# Aquila-2018-Under2.net
KiCad netlist of a schematic drawn in EAGLE
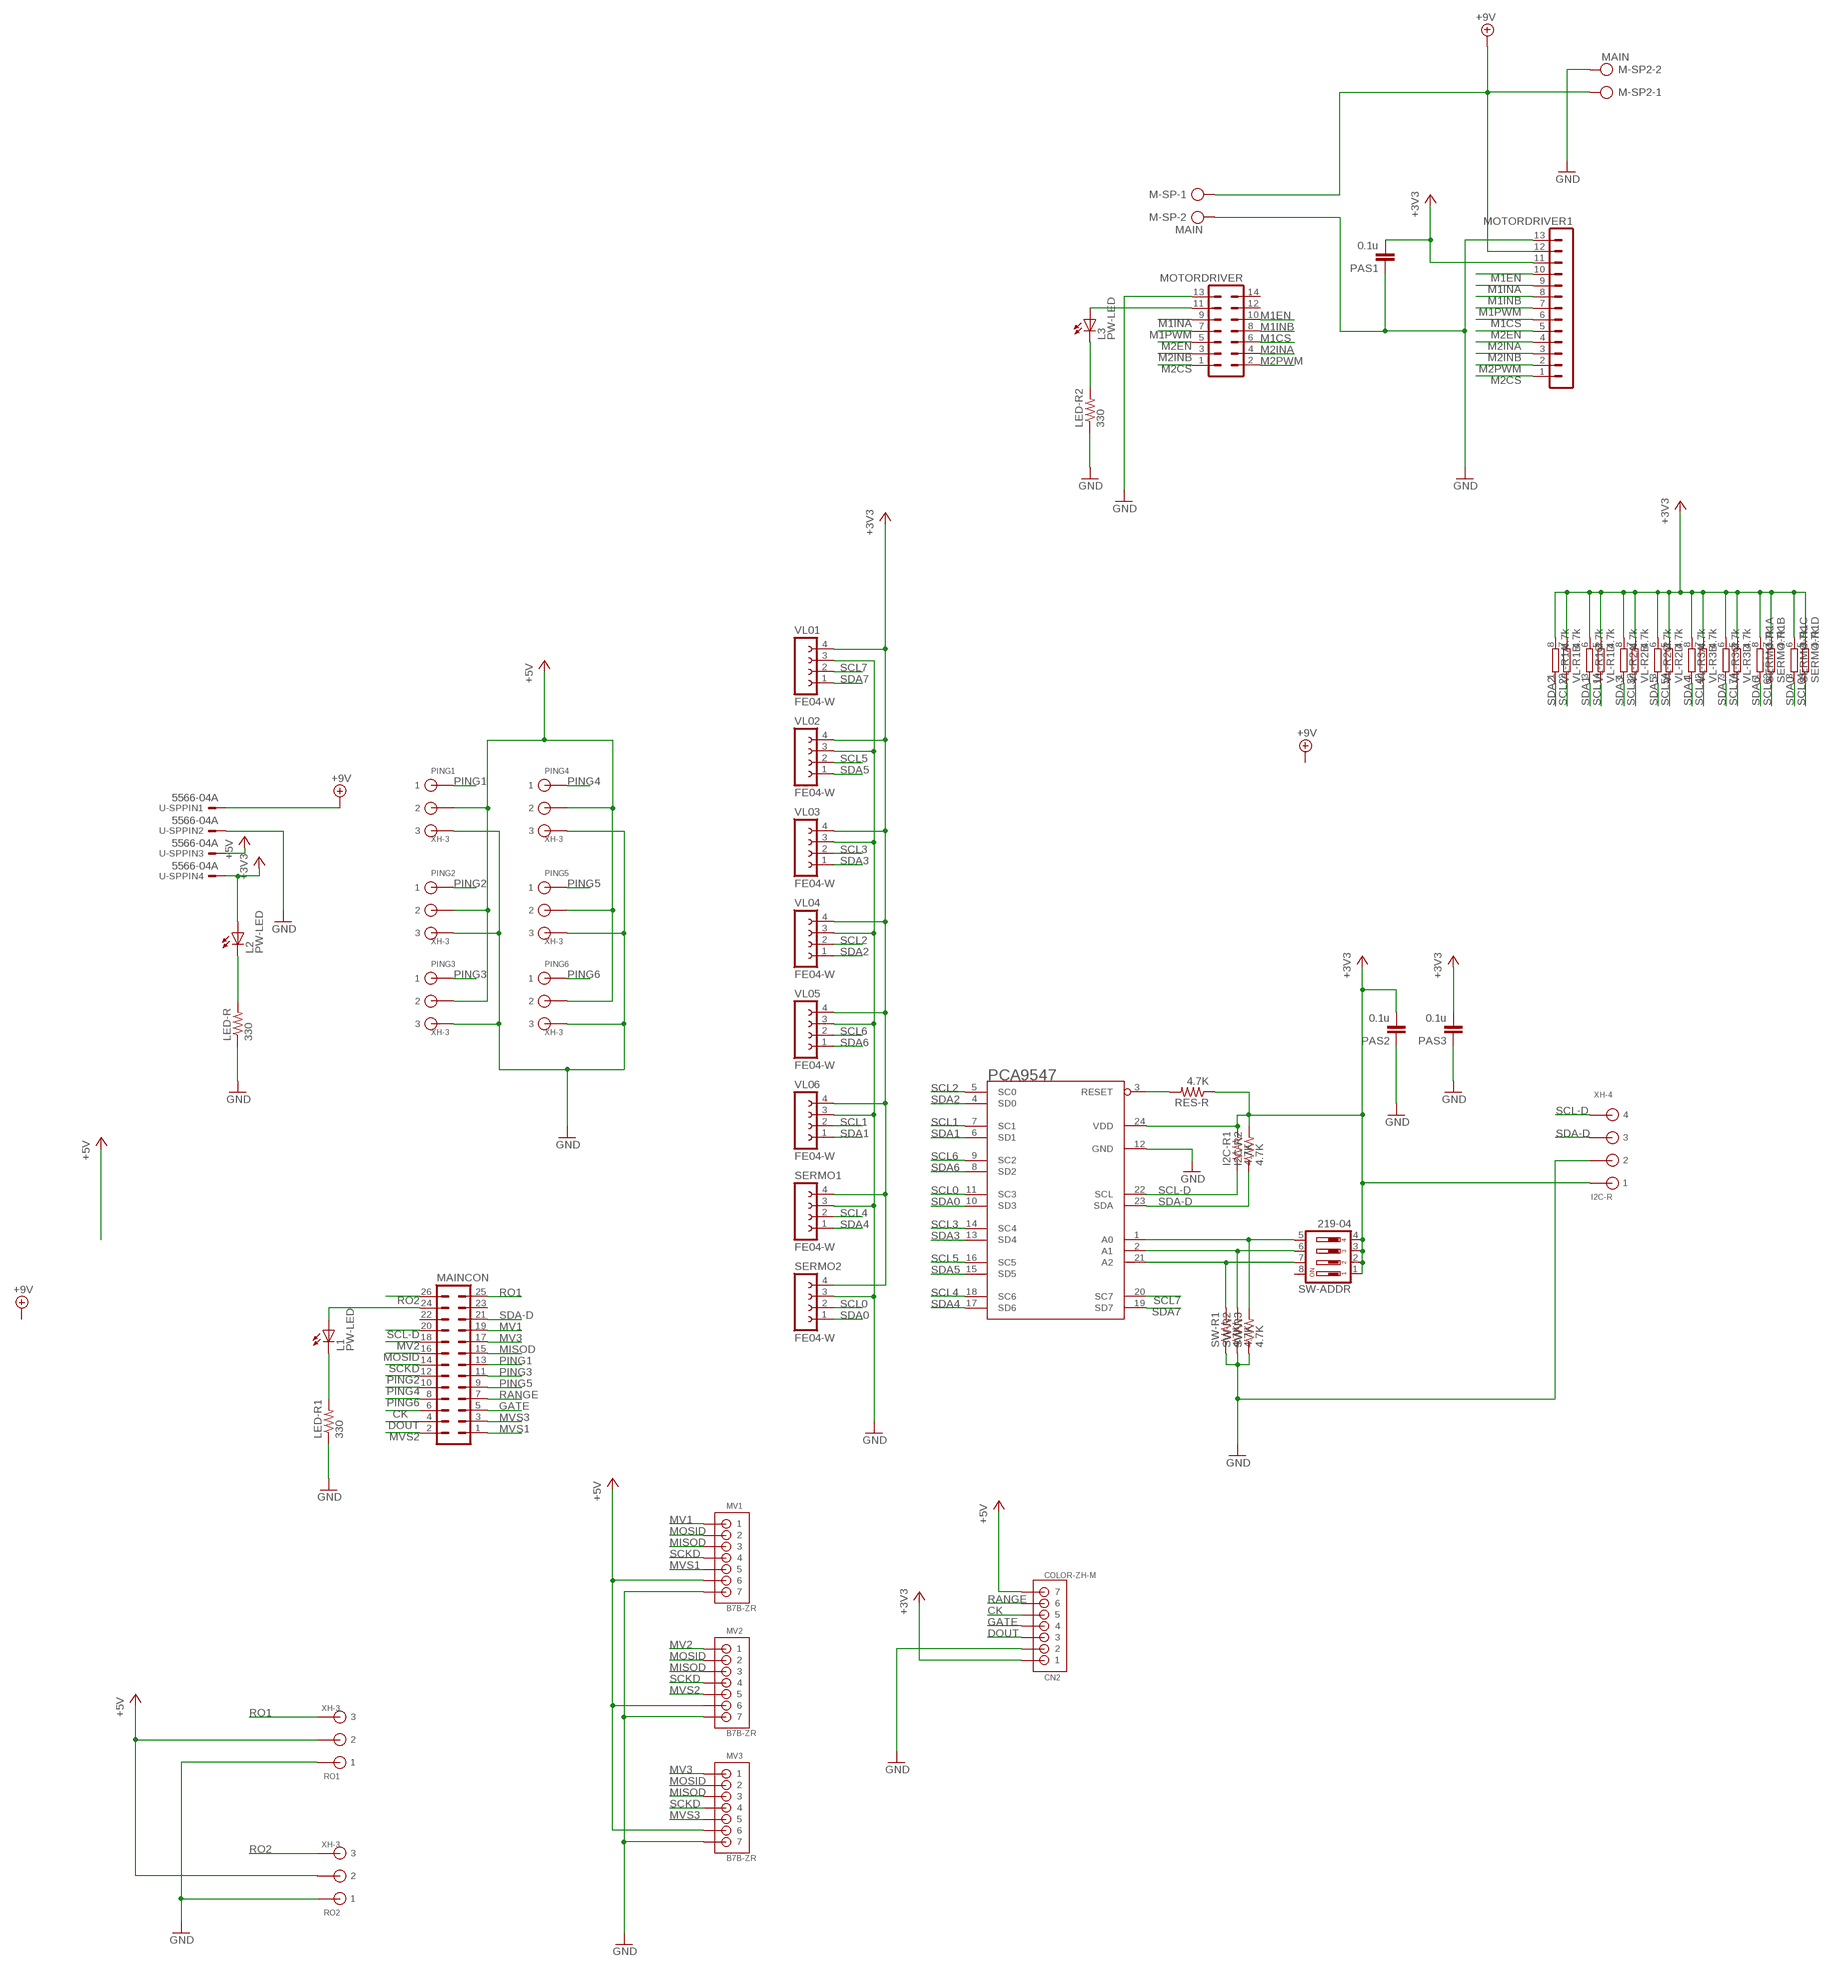
[diagram p0: schematic, sheet 1]

(export (version "E")
  (design (tool "Eeschema 10.0.6"))
  (components
    (comp (ref "CN2")
      (value "COLOR-ZH-M")
      (footprint "eagle-import:B7B-ZR")
      (libsource (lib "eagle-import") (part "B7B-ZR"))
    )
    (comp (ref "I2C-R")
      (value "XH-4")
      (footprint "eagle-import:CON4")
      (libsource (lib "eagle-import") (part "XH-4"))
    )
    (comp (ref "I2C-R1")
      (value "4.7K")
      (footprint "eagle-import:R0805")
      (libsource (lib "eagle-import") (part "R-US_R0805"))
    )
    (comp (ref "I2C-R2")
      (value "4.7K")
      (footprint "eagle-import:R0805")
      (libsource (lib "eagle-import") (part "R-US_R0805"))
    )
    (comp (ref "L1")
      (value "PW-LED")
      (footprint "eagle-import:CHIPLED_0805")
      (libsource (lib "eagle-import") (part "LEDCHIPLED_0805"))
    )
    (comp (ref "L2")
      (value "PW-LED")
      (footprint "eagle-import:CHIPLED_0805")
      (libsource (lib "eagle-import") (part "LEDCHIPLED_0805"))
    )
    (comp (ref "L3")
      (value "PW-LED")
      (footprint "eagle-import:CHIPLED_0805")
      (libsource (lib "eagle-import") (part "LEDCHIPLED_0805"))
    )
    (comp (ref "LED-R")
      (value "330")
      (footprint "eagle-import:R0805")
      (libsource (lib "eagle-import") (part "R-US_R0805"))
    )
    (comp (ref "LED-R1")
      (value "330")
      (footprint "eagle-import:R0805")
      (libsource (lib "eagle-import") (part "R-US_R0805"))
    )
    (comp (ref "LED-R2")
      (value "330")
      (footprint "eagle-import:R0805")
      (libsource (lib "eagle-import") (part "R-US_R0805"))
    )
    (comp (ref "M-SP")
      (value "MAIN")
      (footprint "eagle-import:AK500_2")
      (libsource (lib "eagle-import") (part "AK500/2"))
    )
    (comp (ref "M-SP2")
      (value "MAIN")
      (footprint "eagle-import:AK500_2")
      (libsource (lib "eagle-import") (part "AK500/2"))
    )
    (comp (ref "MAINCON")
      (value "ML26")
      (footprint "eagle-import:ML26")
      (libsource (lib "eagle-import") (part "ML26"))
    )
    (comp (ref "MOTORDRIVER")
      (value "ML14")
      (footprint "eagle-import:ML14")
      (libsource (lib "eagle-import") (part "ML14"))
    )
    (comp (ref "MOTORDRIVER1")
      (value "MA13-1")
      (footprint "eagle-import:MA13-1")
      (libsource (lib "eagle-import") (part "MA13-1"))
    )
    (comp (ref "MV1")
      (value "B7B-ZR")
      (footprint "eagle-import:B7B-ZR")
      (libsource (lib "eagle-import") (part "B7B-ZR"))
    )
    (comp (ref "MV2")
      (value "B7B-ZR")
      (footprint "eagle-import:B7B-ZR")
      (libsource (lib "eagle-import") (part "B7B-ZR"))
    )
    (comp (ref "MV3")
      (value "B7B-ZR")
      (footprint "eagle-import:B7B-ZR")
      (libsource (lib "eagle-import") (part "B7B-ZR"))
    )
    (comp (ref "PAS1")
      (value "0.1u")
      (footprint "eagle-import:C0805")
      (fields (field (name "SPICEPREFIX") "B"))
      (libsource (lib "eagle-import") (part "C-EUC0805"))
    )
    (comp (ref "PAS2")
      (value "0.1u")
      (footprint "eagle-import:C0805")
      (fields (field (name "SPICEPREFIX") "B"))
      (libsource (lib "eagle-import") (part "C-EUC0805"))
    )
    (comp (ref "PAS3")
      (value "0.1u")
      (footprint "eagle-import:C0805")
      (fields (field (name "SPICEPREFIX") "B"))
      (libsource (lib "eagle-import") (part "C-EUC0805"))
    )
    (comp (ref "PCA9547")
      (value "PCA9547")
      (footprint "eagle-import:SO24L")
      (libsource (lib "eagle-import") (part "PCA9547"))
    )
    (comp (ref "PING1")
      (value "XH-3")
      (footprint "eagle-import:CON3")
      (libsource (lib "eagle-import") (part "XH-3"))
    )
    (comp (ref "PING2")
      (value "XH-3")
      (footprint "eagle-import:CON3")
      (libsource (lib "eagle-import") (part "XH-3"))
    )
    (comp (ref "PING3")
      (value "XH-3")
      (footprint "eagle-import:CON3")
      (libsource (lib "eagle-import") (part "XH-3"))
    )
    (comp (ref "PING4")
      (value "XH-3")
      (footprint "eagle-import:CON3")
      (libsource (lib "eagle-import") (part "XH-3"))
    )
    (comp (ref "PING5")
      (value "XH-3")
      (footprint "eagle-import:CON3")
      (libsource (lib "eagle-import") (part "XH-3"))
    )
    (comp (ref "PING6")
      (value "XH-3")
      (footprint "eagle-import:CON3")
      (libsource (lib "eagle-import") (part "XH-3"))
    )
    (comp (ref "RES-R")
      (value "4.7K")
      (footprint "eagle-import:R0805")
      (libsource (lib "eagle-import") (part "R-US_R0805"))
    )
    (comp (ref "RO1")
      (value "XH-3")
      (footprint "eagle-import:CON3")
      (libsource (lib "eagle-import") (part "forprint_XH-3"))
    )
    (comp (ref "RO2")
      (value "XH-3")
      (footprint "eagle-import:CON3")
      (libsource (lib "eagle-import") (part "forprint_XH-3"))
    )
    (comp (ref "SERMO-R1")
      (value "4.7k")
      (footprint "eagle-import:EXB28V")
      (libsource (lib "eagle-import") (part "4R-NEXB28V"))
    )
    (comp (ref "SERMO1")
      (value "FE04-W")
      (footprint "eagle-import:FE04-W")
      (libsource (lib "eagle-import") (part "FE04-W"))
    )
    (comp (ref "SERMO2")
      (value "FE04-W")
      (footprint "eagle-import:FE04-W")
      (libsource (lib "eagle-import") (part "FE04-W"))
    )
    (comp (ref "SW-ADDR")
      (value "219-04")
      (footprint "eagle-import:CTS-219-04")
      (libsource (lib "eagle-import") (part "219-04"))
    )
    (comp (ref "SW-R1")
      (value "4.7K")
      (footprint "eagle-import:R0805")
      (libsource (lib "eagle-import") (part "R-US_R0805"))
    )
    (comp (ref "SW-R2")
      (value "4.7K")
      (footprint "eagle-import:R0805")
      (libsource (lib "eagle-import") (part "R-US_R0805"))
    )
    (comp (ref "SW-R3")
      (value "4.7K")
      (footprint "eagle-import:R0805")
      (libsource (lib "eagle-import") (part "R-US_R0805"))
    )
    (comp (ref "U-SP")
      (value "5566-04A")
      (footprint "eagle-import:5566-04A")
      (libsource (lib "eagle-import") (part "5566-04A"))
    )
    (comp (ref "VL-R1")
      (value "4.7k")
      (footprint "eagle-import:EXB28V")
      (libsource (lib "eagle-import") (part "4R-NEXB28V"))
    )
    (comp (ref "VL-R2")
      (value "4.7k")
      (footprint "eagle-import:EXB28V")
      (libsource (lib "eagle-import") (part "4R-NEXB28V"))
    )
    (comp (ref "VL-R3")
      (value "4.7k")
      (footprint "eagle-import:EXB28V")
      (libsource (lib "eagle-import") (part "4R-NEXB28V"))
    )
    (comp (ref "VL01")
      (value "FE04-W")
      (footprint "eagle-import:FE04-W")
      (libsource (lib "eagle-import") (part "FE04-W"))
    )
    (comp (ref "VL02")
      (value "FE04-W")
      (footprint "eagle-import:FE04-W")
      (libsource (lib "eagle-import") (part "FE04-W"))
    )
    (comp (ref "VL03")
      (value "FE04-W")
      (footprint "eagle-import:FE04-W")
      (libsource (lib "eagle-import") (part "FE04-W"))
    )
    (comp (ref "VL04")
      (value "FE04-W")
      (footprint "eagle-import:FE04-W")
      (libsource (lib "eagle-import") (part "FE04-W"))
    )
    (comp (ref "VL05")
      (value "FE04-W")
      (footprint "eagle-import:FE04-W")
      (libsource (lib "eagle-import") (part "FE04-W"))
    )
    (comp (ref "VL06")
      (value "FE04-W")
      (footprint "eagle-import:FE04-W")
      (libsource (lib "eagle-import") (part "FE04-W"))
    )
  )
  (nets
    (net (code "1") (name "+3V3") (class "Default")
      (node (ref "CN2") (pin "1") (pinfunction "1_1") (pintype "bidirectional"))
      (node (ref "I2C-R") (pin "P$1") (pinfunction "1_P$1") (pintype "bidirectional"))
      (node (ref "I2C-R1") (pin "2") (pinfunction "2_2") (pintype "passive"))
      (node (ref "I2C-R2") (pin "2") (pinfunction "2_2") (pintype "passive"))
      (node (ref "L2") (pin "A") (pinfunction "A_A") (pintype "passive"))
      (node (ref "MOTORDRIVER1") (pin "11") (pinfunction "11_11") (pintype "passive"))
      (node (ref "PAS1") (pin "2") (pinfunction "2_2") (pintype "passive"))
      (node (ref "PAS2") (pin "2") (pinfunction "2_2") (pintype "passive"))
      (node (ref "PAS3") (pin "2") (pinfunction "2_2") (pintype "passive"))
      (node (ref "PCA9547") (pin "24") (pinfunction "VDD_24") (pintype "power_in"))
      (node (ref "RES-R") (pin "1") (pinfunction "1_1") (pintype "passive"))
      (node (ref "SERMO-R1") (pin "5") (pinfunction "2_5") (pintype "passive"))
      (node (ref "SERMO-R1") (pin "6") (pinfunction "2_6") (pintype "passive"))
      (node (ref "SERMO-R1") (pin "7") (pinfunction "2_7") (pintype "passive"))
      (node (ref "SERMO-R1") (pin "8") (pinfunction "2_8") (pintype "passive"))
      (node (ref "SERMO1") (pin "4") (pinfunction "4_4") (pintype "passive"))
      (node (ref "SERMO2") (pin "4") (pinfunction "4_4") (pintype "passive"))
      (node (ref "SW-ADDR") (pin "1") (pinfunction "1_1") (pintype "passive"))
      (node (ref "SW-ADDR") (pin "2") (pinfunction "2_2") (pintype "passive"))
      (node (ref "SW-ADDR") (pin "3") (pinfunction "3_3") (pintype "passive"))
      (node (ref "SW-ADDR") (pin "4") (pinfunction "4_4") (pintype "passive"))
      (node (ref "U-SP") (pin "4") (pinfunction "S_4") (pintype "passive"))
      (node (ref "VL-R1") (pin "5") (pinfunction "2_5") (pintype "passive"))
      (node (ref "VL-R1") (pin "6") (pinfunction "2_6") (pintype "passive"))
      (node (ref "VL-R1") (pin "7") (pinfunction "2_7") (pintype "passive"))
      (node (ref "VL-R1") (pin "8") (pinfunction "2_8") (pintype "passive"))
      (node (ref "VL-R2") (pin "5") (pinfunction "2_5") (pintype "passive"))
      (node (ref "VL-R2") (pin "6") (pinfunction "2_6") (pintype "passive"))
      (node (ref "VL-R2") (pin "7") (pinfunction "2_7") (pintype "passive"))
      (node (ref "VL-R2") (pin "8") (pinfunction "2_8") (pintype "passive"))
      (node (ref "VL-R3") (pin "5") (pinfunction "2_5") (pintype "passive"))
      (node (ref "VL-R3") (pin "6") (pinfunction "2_6") (pintype "passive"))
      (node (ref "VL-R3") (pin "7") (pinfunction "2_7") (pintype "passive"))
      (node (ref "VL-R3") (pin "8") (pinfunction "2_8") (pintype "passive"))
      (node (ref "VL01") (pin "4") (pinfunction "4_4") (pintype "passive"))
      (node (ref "VL02") (pin "4") (pinfunction "4_4") (pintype "passive"))
      (node (ref "VL03") (pin "4") (pinfunction "4_4") (pintype "passive"))
      (node (ref "VL04") (pin "4") (pinfunction "4_4") (pintype "passive"))
      (node (ref "VL05") (pin "4") (pinfunction "4_4") (pintype "passive"))
      (node (ref "VL06") (pin "4") (pinfunction "4_4") (pintype "passive"))
    )
    (net (code "2") (name "+5V") (class "Default")
      (node (ref "CN2") (pin "7") (pinfunction "7_7") (pintype "bidirectional"))
      (node (ref "MV1") (pin "6") (pinfunction "6_6") (pintype "bidirectional"))
      (node (ref "MV2") (pin "6") (pinfunction "6_6") (pintype "bidirectional"))
      (node (ref "MV3") (pin "6") (pinfunction "6_6") (pintype "bidirectional"))
      (node (ref "PING1") (pin "P$2") (pinfunction "2_P$2") (pintype "bidirectional"))
      (node (ref "PING2") (pin "P$2") (pinfunction "2_P$2") (pintype "bidirectional"))
      (node (ref "PING3") (pin "P$2") (pinfunction "2_P$2") (pintype "bidirectional"))
      (node (ref "PING4") (pin "P$2") (pinfunction "2_P$2") (pintype "bidirectional"))
      (node (ref "PING5") (pin "P$2") (pinfunction "2_P$2") (pintype "bidirectional"))
      (node (ref "PING6") (pin "P$2") (pinfunction "2_P$2") (pintype "bidirectional"))
      (node (ref "RO1") (pin "P$2") (pinfunction "2_P$2") (pintype "bidirectional"))
      (node (ref "RO2") (pin "P$2") (pinfunction "2_P$2") (pintype "bidirectional"))
      (node (ref "U-SP") (pin "3") (pinfunction "S_3") (pintype "passive"))
    )
    (net (code "3") (name "+9V") (class "Default")
      (node (ref "M-SP") (pin "1") (pinfunction "KL_1") (pintype "passive"))
      (node (ref "M-SP2") (pin "1") (pinfunction "KL_1") (pintype "passive"))
      (node (ref "MOTORDRIVER1") (pin "12") (pinfunction "12_12") (pintype "passive"))
      (node (ref "U-SP") (pin "1") (pinfunction "S_1") (pintype "passive"))
    )
    (net (code "4") (name "/CK") (class "Default")
      (node (ref "CN2") (pin "5") (pinfunction "5_5") (pintype "bidirectional"))
      (node (ref "MAINCON") (pin "6") (pinfunction "6_6") (pintype "passive"))
    )
    (net (code "5") (name "/DOUT") (class "Default")
      (node (ref "CN2") (pin "3") (pinfunction "3_3") (pintype "bidirectional"))
      (node (ref "MAINCON") (pin "4") (pinfunction "4_4") (pintype "passive"))
    )
    (net (code "6") (name "/GATE") (class "Default")
      (node (ref "CN2") (pin "4") (pinfunction "4_4") (pintype "bidirectional"))
      (node (ref "MAINCON") (pin "5") (pinfunction "5_5") (pintype "passive"))
    )
    (net (code "7") (name "/M1CS") (class "Default")
      (node (ref "MOTORDRIVER") (pin "6") (pinfunction "6_6") (pintype "passive"))
      (node (ref "MOTORDRIVER1") (pin "6") (pinfunction "6_6") (pintype "passive"))
    )
    (net (code "8") (name "/M1EN") (class "Default")
      (node (ref "MOTORDRIVER") (pin "10") (pinfunction "10_10") (pintype "passive"))
      (node (ref "MOTORDRIVER1") (pin "10") (pinfunction "10_10") (pintype "passive"))
    )
    (net (code "9") (name "/M1INA") (class "Default")
      (node (ref "MOTORDRIVER") (pin "9") (pinfunction "9_9") (pintype "passive"))
      (node (ref "MOTORDRIVER1") (pin "9") (pinfunction "9_9") (pintype "passive"))
    )
    (net (code "10") (name "/M1INB") (class "Default")
      (node (ref "MOTORDRIVER") (pin "8") (pinfunction "8_8") (pintype "passive"))
      (node (ref "MOTORDRIVER1") (pin "8") (pinfunction "8_8") (pintype "passive"))
    )
    (net (code "11") (name "/M1PWM") (class "Default")
      (node (ref "MOTORDRIVER") (pin "7") (pinfunction "7_7") (pintype "passive"))
      (node (ref "MOTORDRIVER1") (pin "7") (pinfunction "7_7") (pintype "passive"))
    )
    (net (code "12") (name "/M2CS") (class "Default")
      (node (ref "MOTORDRIVER") (pin "1") (pinfunction "1_1") (pintype "passive"))
      (node (ref "MOTORDRIVER1") (pin "1") (pinfunction "1_1") (pintype "passive"))
    )
    (net (code "13") (name "/M2EN") (class "Default")
      (node (ref "MOTORDRIVER") (pin "5") (pinfunction "5_5") (pintype "passive"))
      (node (ref "MOTORDRIVER1") (pin "5") (pinfunction "5_5") (pintype "passive"))
    )
    (net (code "14") (name "/M2INA") (class "Default")
      (node (ref "MOTORDRIVER") (pin "4") (pinfunction "4_4") (pintype "passive"))
      (node (ref "MOTORDRIVER1") (pin "4") (pinfunction "4_4") (pintype "passive"))
    )
    (net (code "15") (name "/M2INB") (class "Default")
      (node (ref "MOTORDRIVER") (pin "3") (pinfunction "3_3") (pintype "passive"))
      (node (ref "MOTORDRIVER1") (pin "3") (pinfunction "3_3") (pintype "passive"))
    )
    (net (code "16") (name "/M2PWM") (class "Default")
      (node (ref "MOTORDRIVER") (pin "2") (pinfunction "2_2") (pintype "passive"))
      (node (ref "MOTORDRIVER1") (pin "2") (pinfunction "2_2") (pintype "passive"))
    )
    (net (code "17") (name "/MISOD") (class "Default")
      (node (ref "MAINCON") (pin "15") (pinfunction "15_15") (pintype "passive"))
      (node (ref "MV1") (pin "3") (pinfunction "3_3") (pintype "bidirectional"))
      (node (ref "MV2") (pin "3") (pinfunction "3_3") (pintype "bidirectional"))
      (node (ref "MV3") (pin "3") (pinfunction "3_3") (pintype "bidirectional"))
    )
    (net (code "18") (name "/MOSID") (class "Default")
      (node (ref "MAINCON") (pin "16") (pinfunction "16_16") (pintype "passive"))
      (node (ref "MV1") (pin "2") (pinfunction "2_2") (pintype "bidirectional"))
      (node (ref "MV2") (pin "2") (pinfunction "2_2") (pintype "bidirectional"))
      (node (ref "MV3") (pin "2") (pinfunction "2_2") (pintype "bidirectional"))
    )
    (net (code "19") (name "/MV1") (class "Default")
      (node (ref "MAINCON") (pin "19") (pinfunction "19_19") (pintype "passive"))
      (node (ref "MV1") (pin "1") (pinfunction "1_1") (pintype "bidirectional"))
    )
    (net (code "20") (name "/MV2") (class "Default")
      (node (ref "MAINCON") (pin "18") (pinfunction "18_18") (pintype "passive"))
      (node (ref "MV2") (pin "1") (pinfunction "1_1") (pintype "bidirectional"))
    )
    (net (code "21") (name "/MV3") (class "Default")
      (node (ref "MAINCON") (pin "17") (pinfunction "17_17") (pintype "passive"))
      (node (ref "MV3") (pin "1") (pinfunction "1_1") (pintype "bidirectional"))
    )
    (net (code "22") (name "/MVS1") (class "Default")
      (node (ref "MAINCON") (pin "1") (pinfunction "1_1") (pintype "passive"))
      (node (ref "MV1") (pin "5") (pinfunction "5_5") (pintype "bidirectional"))
    )
    (net (code "23") (name "/MVS2") (class "Default")
      (node (ref "MAINCON") (pin "2") (pinfunction "2_2") (pintype "passive"))
      (node (ref "MV2") (pin "5") (pinfunction "5_5") (pintype "bidirectional"))
    )
    (net (code "24") (name "/MVS3") (class "Default")
      (node (ref "MAINCON") (pin "3") (pinfunction "3_3") (pintype "passive"))
      (node (ref "MV3") (pin "5") (pinfunction "5_5") (pintype "bidirectional"))
    )
    (net (code "25") (name "/PING1") (class "Default")
      (node (ref "MAINCON") (pin "13") (pinfunction "13_13") (pintype "passive"))
      (node (ref "PING1") (pin "P$1") (pinfunction "1_P$1") (pintype "bidirectional"))
    )
    (net (code "26") (name "/PING2") (class "Default")
      (node (ref "MAINCON") (pin "12") (pinfunction "12_12") (pintype "passive"))
      (node (ref "PING2") (pin "P$1") (pinfunction "1_P$1") (pintype "bidirectional"))
    )
    (net (code "27") (name "/PING3") (class "Default")
      (node (ref "MAINCON") (pin "11") (pinfunction "11_11") (pintype "passive"))
      (node (ref "PING3") (pin "P$1") (pinfunction "1_P$1") (pintype "bidirectional"))
    )
    (net (code "28") (name "/PING4") (class "Default")
      (node (ref "MAINCON") (pin "10") (pinfunction "10_10") (pintype "passive"))
      (node (ref "PING4") (pin "P$1") (pinfunction "1_P$1") (pintype "bidirectional"))
    )
    (net (code "29") (name "/PING5") (class "Default")
      (node (ref "MAINCON") (pin "9") (pinfunction "9_9") (pintype "passive"))
      (node (ref "PING5") (pin "P$1") (pinfunction "1_P$1") (pintype "bidirectional"))
    )
    (net (code "30") (name "/PING6") (class "Default")
      (node (ref "MAINCON") (pin "8") (pinfunction "8_8") (pintype "passive"))
      (node (ref "PING6") (pin "P$1") (pinfunction "1_P$1") (pintype "bidirectional"))
    )
    (net (code "31") (name "/RANGE") (class "Default")
      (node (ref "CN2") (pin "6") (pinfunction "6_6") (pintype "bidirectional"))
      (node (ref "MAINCON") (pin "7") (pinfunction "7_7") (pintype "passive"))
    )
    (net (code "32") (name "/RO1") (class "Default")
      (node (ref "MAINCON") (pin "25") (pinfunction "25_25") (pintype "passive"))
      (node (ref "RO1") (pin "P$3") (pinfunction "3_P$3") (pintype "bidirectional"))
    )
    (net (code "33") (name "/RO2") (class "Default")
      (node (ref "MAINCON") (pin "26") (pinfunction "26_26") (pintype "passive"))
      (node (ref "RO2") (pin "P$3") (pinfunction "3_P$3") (pintype "bidirectional"))
    )
    (net (code "34") (name "/SCKD") (class "Default")
      (node (ref "MAINCON") (pin "14") (pinfunction "14_14") (pintype "passive"))
      (node (ref "MV1") (pin "4") (pinfunction "4_4") (pintype "bidirectional"))
      (node (ref "MV2") (pin "4") (pinfunction "4_4") (pintype "bidirectional"))
      (node (ref "MV3") (pin "4") (pinfunction "4_4") (pintype "bidirectional"))
    )
    (net (code "35") (name "/SCL-D") (class "Default")
      (node (ref "I2C-R") (pin "P$4") (pinfunction "4_P$4") (pintype "bidirectional"))
      (node (ref "I2C-R1") (pin "1") (pinfunction "1_1") (pintype "passive"))
      (node (ref "MAINCON") (pin "20") (pinfunction "20_20") (pintype "passive"))
      (node (ref "PCA9547") (pin "22") (pinfunction "SCL_22") (pintype "bidirectional"))
    )
    (net (code "36") (name "/SCL0") (class "Default")
      (node (ref "PCA9547") (pin "11") (pinfunction "SC3_11") (pintype "bidirectional"))
      (node (ref "SERMO-R1") (pin "4") (pinfunction "1_4") (pintype "passive"))
      (node (ref "SERMO2") (pin "2") (pinfunction "2_2") (pintype "passive"))
    )
    (net (code "37") (name "/SCL1") (class "Default")
      (node (ref "PCA9547") (pin "7") (pinfunction "SC1_7") (pintype "bidirectional"))
      (node (ref "VL-R1") (pin "4") (pinfunction "1_4") (pintype "passive"))
      (node (ref "VL06") (pin "2") (pinfunction "2_2") (pintype "passive"))
    )
    (net (code "38") (name "/SCL2") (class "Default")
      (node (ref "PCA9547") (pin "5") (pinfunction "SC0_5") (pintype "bidirectional"))
      (node (ref "VL-R1") (pin "2") (pinfunction "1_2") (pintype "passive"))
      (node (ref "VL04") (pin "2") (pinfunction "2_2") (pintype "passive"))
    )
    (net (code "39") (name "/SCL3") (class "Default")
      (node (ref "PCA9547") (pin "14") (pinfunction "SC4_14") (pintype "bidirectional"))
      (node (ref "VL-R2") (pin "2") (pinfunction "1_2") (pintype "passive"))
      (node (ref "VL03") (pin "2") (pinfunction "2_2") (pintype "passive"))
    )
    (net (code "40") (name "/SCL4") (class "Default")
      (node (ref "PCA9547") (pin "18") (pinfunction "SC6_18") (pintype "bidirectional"))
      (node (ref "SERMO1") (pin "2") (pinfunction "2_2") (pintype "passive"))
      (node (ref "VL-R3") (pin "2") (pinfunction "1_2") (pintype "passive"))
    )
    (net (code "41") (name "/SCL5") (class "Default")
      (node (ref "PCA9547") (pin "16") (pinfunction "SC5_16") (pintype "bidirectional"))
      (node (ref "VL-R2") (pin "4") (pinfunction "1_4") (pintype "passive"))
      (node (ref "VL02") (pin "2") (pinfunction "2_2") (pintype "passive"))
    )
    (net (code "42") (name "/SCL6") (class "Default")
      (node (ref "PCA9547") (pin "9") (pinfunction "SC2_9") (pintype "bidirectional"))
      (node (ref "SERMO-R1") (pin "2") (pinfunction "1_2") (pintype "passive"))
      (node (ref "VL05") (pin "2") (pinfunction "2_2") (pintype "passive"))
    )
    (net (code "43") (name "/SCL7") (class "Default")
      (node (ref "PCA9547") (pin "20") (pinfunction "SC7_20") (pintype "bidirectional"))
      (node (ref "VL-R3") (pin "4") (pinfunction "1_4") (pintype "passive"))
      (node (ref "VL01") (pin "2") (pinfunction "2_2") (pintype "passive"))
    )
    (net (code "44") (name "/SDA-D") (class "Default")
      (node (ref "I2C-R") (pin "P$3") (pinfunction "3_P$3") (pintype "bidirectional"))
      (node (ref "I2C-R2") (pin "1") (pinfunction "1_1") (pintype "passive"))
      (node (ref "MAINCON") (pin "21") (pinfunction "21_21") (pintype "passive"))
      (node (ref "PCA9547") (pin "23") (pinfunction "SDA_23") (pintype "bidirectional"))
    )
    (net (code "45") (name "/SDA0") (class "Default")
      (node (ref "PCA9547") (pin "10") (pinfunction "SD3_10") (pintype "bidirectional"))
      (node (ref "SERMO-R1") (pin "3") (pinfunction "1_3") (pintype "passive"))
      (node (ref "SERMO2") (pin "1") (pinfunction "1_1") (pintype "passive"))
    )
    (net (code "46") (name "/SDA1") (class "Default")
      (node (ref "PCA9547") (pin "6") (pinfunction "SD1_6") (pintype "bidirectional"))
      (node (ref "VL-R1") (pin "3") (pinfunction "1_3") (pintype "passive"))
      (node (ref "VL06") (pin "1") (pinfunction "1_1") (pintype "passive"))
    )
    (net (code "47") (name "/SDA2") (class "Default")
      (node (ref "PCA9547") (pin "4") (pinfunction "SD0_4") (pintype "bidirectional"))
      (node (ref "VL-R1") (pin "1") (pinfunction "1_1") (pintype "passive"))
      (node (ref "VL04") (pin "1") (pinfunction "1_1") (pintype "passive"))
    )
    (net (code "48") (name "/SDA3") (class "Default")
      (node (ref "PCA9547") (pin "13") (pinfunction "SD4_13") (pintype "bidirectional"))
      (node (ref "VL-R2") (pin "1") (pinfunction "1_1") (pintype "passive"))
      (node (ref "VL03") (pin "1") (pinfunction "1_1") (pintype "passive"))
    )
    (net (code "49") (name "/SDA4") (class "Default")
      (node (ref "PCA9547") (pin "17") (pinfunction "SD6_17") (pintype "bidirectional"))
      (node (ref "SERMO1") (pin "1") (pinfunction "1_1") (pintype "passive"))
      (node (ref "VL-R3") (pin "1") (pinfunction "1_1") (pintype "passive"))
    )
    (net (code "50") (name "/SDA5") (class "Default")
      (node (ref "PCA9547") (pin "15") (pinfunction "SD5_15") (pintype "bidirectional"))
      (node (ref "VL-R2") (pin "3") (pinfunction "1_3") (pintype "passive"))
      (node (ref "VL02") (pin "1") (pinfunction "1_1") (pintype "passive"))
    )
    (net (code "51") (name "/SDA6") (class "Default")
      (node (ref "PCA9547") (pin "8") (pinfunction "SD2_8") (pintype "bidirectional"))
      (node (ref "SERMO-R1") (pin "1") (pinfunction "1_1") (pintype "passive"))
      (node (ref "VL05") (pin "1") (pinfunction "1_1") (pintype "passive"))
    )
    (net (code "52") (name "/SDA7") (class "Default")
      (node (ref "PCA9547") (pin "19") (pinfunction "SD7_19") (pintype "bidirectional"))
      (node (ref "VL-R3") (pin "3") (pinfunction "1_3") (pintype "passive"))
      (node (ref "VL01") (pin "1") (pinfunction "1_1") (pintype "passive"))
    )
    (net (code "53") (name "GND") (class "Default")
      (node (ref "CN2") (pin "2") (pinfunction "2_2") (pintype "bidirectional"))
      (node (ref "I2C-R") (pin "P$2") (pinfunction "2_P$2") (pintype "bidirectional"))
      (node (ref "LED-R") (pin "1") (pinfunction "1_1") (pintype "passive"))
      (node (ref "LED-R1") (pin "1") (pinfunction "1_1") (pintype "passive"))
      (node (ref "LED-R2") (pin "1") (pinfunction "1_1") (pintype "passive"))
      (node (ref "M-SP") (pin "2") (pinfunction "KL_2") (pintype "passive"))
      (node (ref "M-SP2") (pin "2") (pinfunction "KL_2") (pintype "passive"))
      (node (ref "MOTORDRIVER") (pin "13") (pinfunction "13_13") (pintype "passive"))
      (node (ref "MOTORDRIVER1") (pin "13") (pinfunction "13_13") (pintype "passive"))
      (node (ref "MV1") (pin "7") (pinfunction "7_7") (pintype "bidirectional"))
      (node (ref "MV2") (pin "7") (pinfunction "7_7") (pintype "bidirectional"))
      (node (ref "MV3") (pin "7") (pinfunction "7_7") (pintype "bidirectional"))
      (node (ref "PAS1") (pin "1") (pinfunction "1_1") (pintype "passive"))
      (node (ref "PAS2") (pin "1") (pinfunction "1_1") (pintype "passive"))
      (node (ref "PAS3") (pin "1") (pinfunction "1_1") (pintype "passive"))
      (node (ref "PCA9547") (pin "12") (pinfunction "GND_12") (pintype "power_in"))
      (node (ref "PING1") (pin "P$3") (pinfunction "3_P$3") (pintype "bidirectional"))
      (node (ref "PING2") (pin "P$3") (pinfunction "3_P$3") (pintype "bidirectional"))
      (node (ref "PING3") (pin "P$3") (pinfunction "3_P$3") (pintype "bidirectional"))
      (node (ref "PING4") (pin "P$3") (pinfunction "3_P$3") (pintype "bidirectional"))
      (node (ref "PING5") (pin "P$3") (pinfunction "3_P$3") (pintype "bidirectional"))
      (node (ref "PING6") (pin "P$3") (pinfunction "3_P$3") (pintype "bidirectional"))
      (node (ref "RO1") (pin "P$1") (pinfunction "1_P$1") (pintype "bidirectional"))
      (node (ref "RO2") (pin "P$1") (pinfunction "1_P$1") (pintype "bidirectional"))
      (node (ref "SERMO1") (pin "3") (pinfunction "3_3") (pintype "passive"))
      (node (ref "SERMO2") (pin "3") (pinfunction "3_3") (pintype "passive"))
      (node (ref "SW-R1") (pin "1") (pinfunction "1_1") (pintype "passive"))
      (node (ref "SW-R2") (pin "1") (pinfunction "1_1") (pintype "passive"))
      (node (ref "SW-R3") (pin "1") (pinfunction "1_1") (pintype "passive"))
      (node (ref "U-SP") (pin "2") (pinfunction "S_2") (pintype "passive"))
      (node (ref "VL01") (pin "3") (pinfunction "3_3") (pintype "passive"))
      (node (ref "VL02") (pin "3") (pinfunction "3_3") (pintype "passive"))
      (node (ref "VL03") (pin "3") (pinfunction "3_3") (pintype "passive"))
      (node (ref "VL04") (pin "3") (pinfunction "3_3") (pintype "passive"))
      (node (ref "VL05") (pin "3") (pinfunction "3_3") (pintype "passive"))
      (node (ref "VL06") (pin "3") (pinfunction "3_3") (pintype "passive"))
    )
    (net (code "54") (name "Net-(L1-PadA)") (class "Default")
      (node (ref "L1") (pin "A") (pinfunction "A_A") (pintype "passive"))
      (node (ref "MAINCON") (pin "24") (pinfunction "24_24") (pintype "passive"))
    )
    (net (code "55") (name "Net-(L1-PadC)") (class "Default")
      (node (ref "L1") (pin "C") (pinfunction "C_C") (pintype "passive"))
      (node (ref "LED-R1") (pin "2") (pinfunction "2_2") (pintype "passive"))
    )
    (net (code "56") (name "Net-(L2-PadC)") (class "Default")
      (node (ref "L2") (pin "C") (pinfunction "C_C") (pintype "passive"))
      (node (ref "LED-R") (pin "2") (pinfunction "2_2") (pintype "passive"))
    )
    (net (code "57") (name "Net-(L3-PadA)") (class "Default")
      (node (ref "L3") (pin "A") (pinfunction "A_A") (pintype "passive"))
      (node (ref "MOTORDRIVER") (pin "11") (pinfunction "11_11") (pintype "passive"))
    )
    (net (code "58") (name "Net-(L3-PadC)") (class "Default")
      (node (ref "L3") (pin "C") (pinfunction "C_C") (pintype "passive"))
      (node (ref "LED-R2") (pin "2") (pinfunction "2_2") (pintype "passive"))
    )
    (net (code "59") (name "Net-(PCA9547-A0)") (class "Default")
      (node (ref "PCA9547") (pin "1") (pinfunction "A0_1") (pintype "input"))
      (node (ref "SW-ADDR") (pin "5") (pinfunction "5_5") (pintype "passive"))
      (node (ref "SW-R3") (pin "2") (pinfunction "2_2") (pintype "passive"))
    )
    (net (code "60") (name "Net-(PCA9547-A1)") (class "Default")
      (node (ref "PCA9547") (pin "2") (pinfunction "A1_2") (pintype "input"))
      (node (ref "SW-ADDR") (pin "6") (pinfunction "6_6") (pintype "passive"))
      (node (ref "SW-R2") (pin "2") (pinfunction "2_2") (pintype "passive"))
    )
    (net (code "61") (name "Net-(PCA9547-A2)") (class "Default")
      (node (ref "PCA9547") (pin "21") (pinfunction "A2_21") (pintype "input"))
      (node (ref "SW-ADDR") (pin "7") (pinfunction "7_7") (pintype "passive"))
      (node (ref "SW-R1") (pin "2") (pinfunction "2_2") (pintype "passive"))
    )
    (net (code "62") (name "Net-(PCA9547-RESET)") (class "Default")
      (node (ref "PCA9547") (pin "3") (pinfunction "RESET_3") (pintype "bidirectional"))
      (node (ref "RES-R") (pin "2") (pinfunction "2_2") (pintype "passive"))
    )
    (net (code "63") (name "unconnected-(MAINCON-Pad22)") (class "Default")
      (node (ref "MAINCON") (pin "22") (pinfunction "22_22") (pintype "passive"))
    )
    (net (code "64") (name "unconnected-(MAINCON-Pad23)") (class "Default")
      (node (ref "MAINCON") (pin "23") (pinfunction "23_23") (pintype "passive"))
    )
    (net (code "65") (name "unconnected-(MOTORDRIVER-Pad12)") (class "Default")
      (node (ref "MOTORDRIVER") (pin "12") (pinfunction "12_12") (pintype "passive"))
    )
    (net (code "66") (name "unconnected-(MOTORDRIVER-Pad14)") (class "Default")
      (node (ref "MOTORDRIVER") (pin "14") (pinfunction "14_14") (pintype "passive"))
    )
    (net (code "67") (name "unconnected-(SW-ADDR-Pad8)") (class "Default")
      (node (ref "SW-ADDR") (pin "8") (pinfunction "8_8") (pintype "passive"))
    )
  )
)
